# RTI-Dome.net
KiCad netlist of a schematic drawn in EAGLE
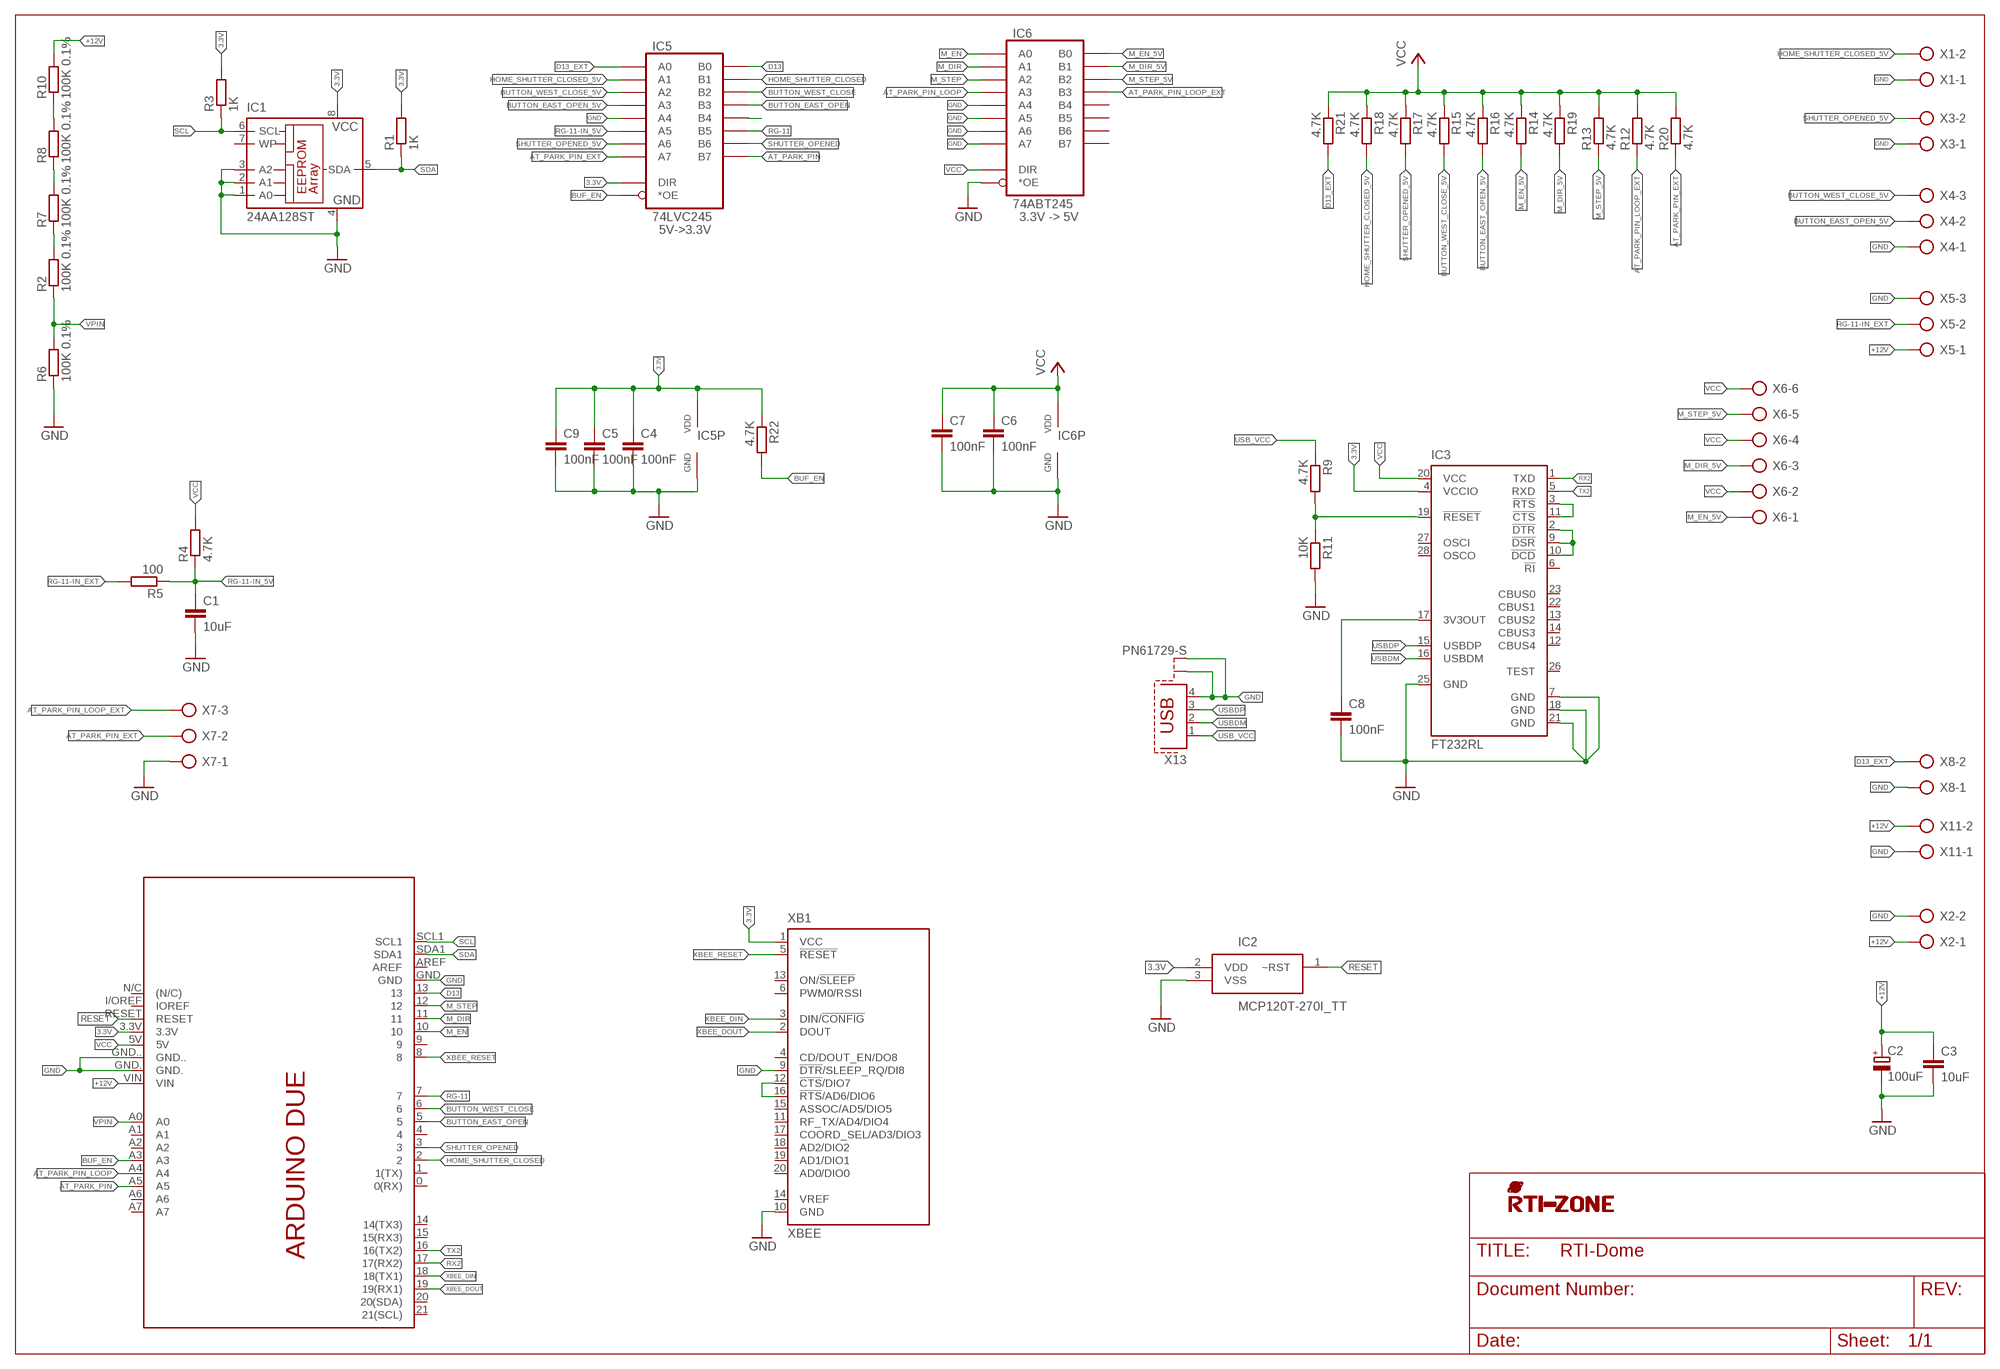
[diagram p0: schematic, sheet 1]

(export (version "E")
  (design (tool "Eeschema 10.0.6"))
  (components
    (comp (ref "C1")
      (value "10uF")
      (footprint "eagle-import:C0805")
      (libsource (lib "eagle-import") (part "C-EU'0805'"))
    )
    (comp (ref "C2")
      (value "100uF")
      (footprint "eagle-import:UD-10X10_NICHICON")
      (libsource (lib "eagle-import") (part "CPOL-EU"))
    )
    (comp (ref "C3")
      (value "10uF")
      (footprint "eagle-import:C0805")
      (libsource (lib "eagle-import") (part "C-EU'0805'"))
    )
    (comp (ref "C4")
      (value "100nF")
      (footprint "eagle-import:C0805")
      (libsource (lib "eagle-import") (part "C-EU'0805'"))
    )
    (comp (ref "C5")
      (value "100nF")
      (footprint "eagle-import:C0805")
      (libsource (lib "eagle-import") (part "C-EU'0805'"))
    )
    (comp (ref "C6")
      (value "100nF")
      (footprint "eagle-import:C0805")
      (libsource (lib "eagle-import") (part "C-EU'0805'"))
    )
    (comp (ref "C7")
      (value "100nF")
      (footprint "eagle-import:C0805")
      (libsource (lib "eagle-import") (part "C-EU'0805'"))
    )
    (comp (ref "C8")
      (value "100nF")
      (footprint "eagle-import:C0805")
      (libsource (lib "eagle-import") (part "C-EU'0805'"))
    )
    (comp (ref "C9")
      (value "100nF")
      (footprint "eagle-import:C0805")
      (libsource (lib "eagle-import") (part "C-EU'0805'"))
    )
    (comp (ref "IC1")
      (value "24AA128ST")
      (footprint "eagle-import:TSSOP8")
      (fields (field (name "MF") "MICROCHIP") (field (name "MPN") "24AA128-I/ST"))
      (libsource (lib "eagle-import") (part "24STAA128"))
    )
    (comp (ref "IC2")
      (value "MCP120T-270I_TT")
      (footprint "eagle-import:SOT95P237X112-3N")
      (fields
        (field (name "MANUFACTURER_PART_NUMBER") "MCP120T-270I/TT")
        (field (name "MOUSER_PART_NUMBER") "579-MCP120T-270I/TT")
      )
      (libsource (lib "eagle-import") (part "MCP120T-270I_TT"))
    )
    (comp (ref "IC3")
      (value "FT232RL")
      (footprint "eagle-import:SSOP28")
      (libsource (lib "eagle-import") (part "FT232RL"))
    )
    (comp (ref "IC5")
      (value "74LVC245")
      (footprint "eagle-import:TSSOP20")
      (libsource (lib "eagle-import") (part "74245LVC"))
    )
    (comp (ref "IC6")
      (value "74ABT245")
      (footprint "eagle-import:TSSOP20")
      (libsource (lib "eagle-import") (part "74245ABT"))
    )
    (comp (ref "PCB1")
      (value "ARDUINO_DUE_SHIELD_SHORT")
      (footprint "eagle-import:ARDUINO_DUE_SHIELD_SHORT")
      (libsource (lib "eagle-import") (part "ARDUINO_DUE_SHIELD_SHORT"))
    )
    (comp (ref "R1")
      (value "1K")
      (footprint "eagle-import:R0805")
      (libsource (lib "eagle-import") (part "R-EU'0805'"))
    )
    (comp (ref "R2")
      (value "100K 0.1%")
      (footprint "eagle-import:R0805")
      (libsource (lib "eagle-import") (part "R-EU'0805'"))
    )
    (comp (ref "R3")
      (value "1K")
      (footprint "eagle-import:R0805")
      (libsource (lib "eagle-import") (part "R-EU'0805'"))
    )
    (comp (ref "R4")
      (value "4.7K")
      (footprint "eagle-import:R0805")
      (libsource (lib "eagle-import") (part "R-EU'0805'"))
    )
    (comp (ref "R5")
      (value "100")
      (footprint "eagle-import:R0805")
      (libsource (lib "eagle-import") (part "R-EU'0805'"))
    )
    (comp (ref "R6")
      (value "100K 0.1%")
      (footprint "eagle-import:R0805")
      (libsource (lib "eagle-import") (part "R-EU'0805'"))
    )
    (comp (ref "R7")
      (value "100K 0.1%")
      (footprint "eagle-import:R0805")
      (libsource (lib "eagle-import") (part "R-EU'0805'"))
    )
    (comp (ref "R8")
      (value "100K 0.1%")
      (footprint "eagle-import:R0805")
      (libsource (lib "eagle-import") (part "R-EU'0805'"))
    )
    (comp (ref "R9")
      (value "4.7K")
      (footprint "eagle-import:R0805")
      (libsource (lib "eagle-import") (part "R-EU'0805'"))
    )
    (comp (ref "R10")
      (value "100K 0.1%")
      (footprint "eagle-import:R0805")
      (libsource (lib "eagle-import") (part "R-EU'0805'"))
    )
    (comp (ref "R11")
      (value "10K")
      (footprint "eagle-import:R0805")
      (libsource (lib "eagle-import") (part "R-EU'0805'"))
    )
    (comp (ref "R12")
      (value "4.7K")
      (footprint "eagle-import:R0805")
      (libsource (lib "eagle-import") (part "R-EU'0805'"))
    )
    (comp (ref "R13")
      (value "4.7K")
      (footprint "eagle-import:R0805")
      (libsource (lib "eagle-import") (part "R-EU'0805'"))
    )
    (comp (ref "R14")
      (value "4.7K")
      (footprint "eagle-import:R0805")
      (libsource (lib "eagle-import") (part "R-EU'0805'"))
    )
    (comp (ref "R15")
      (value "4.7K")
      (footprint "eagle-import:R0805")
      (libsource (lib "eagle-import") (part "R-EU'0805'"))
    )
    (comp (ref "R16")
      (value "4.7K")
      (footprint "eagle-import:R0805")
      (libsource (lib "eagle-import") (part "R-EU'0805'"))
    )
    (comp (ref "R17")
      (value "4.7K")
      (footprint "eagle-import:R0805")
      (libsource (lib "eagle-import") (part "R-EU'0805'"))
    )
    (comp (ref "R18")
      (value "4.7K")
      (footprint "eagle-import:R0805")
      (libsource (lib "eagle-import") (part "R-EU'0805'"))
    )
    (comp (ref "R19")
      (value "4.7K")
      (footprint "eagle-import:R0805")
      (libsource (lib "eagle-import") (part "R-EU'0805'"))
    )
    (comp (ref "R20")
      (value "4.7K")
      (footprint "eagle-import:R0805")
      (libsource (lib "eagle-import") (part "R-EU'0805'"))
    )
    (comp (ref "R21")
      (value "4.7K")
      (footprint "eagle-import:R0805")
      (libsource (lib "eagle-import") (part "R-EU'0805'"))
    )
    (comp (ref "R22")
      (value "4.7K")
      (footprint "eagle-import:R0805")
      (libsource (lib "eagle-import") (part "R-EU'0805'"))
    )
    (comp (ref "U$4")
      (value "RTI-LOGO_BIG")
      (footprint "eagle-import:LOGO_BIG")
      (libsource (lib "eagle-import") (part "RTI-LOGO_BIG"))
    )
    (comp (ref "X1")
      (value "AK500/2")
      (footprint "eagle-import:AK500_2")
      (libsource (lib "eagle-import") (part "AK500/2"))
    )
    (comp (ref "X2")
      (value "AK500/2")
      (footprint "eagle-import:AK500_2")
      (libsource (lib "eagle-import") (part "AK500/2"))
    )
    (comp (ref "X3")
      (value "AK500/2")
      (footprint "eagle-import:AK500_2")
      (libsource (lib "eagle-import") (part "AK500/2"))
    )
    (comp (ref "X4")
      (value "AK500/3")
      (footprint "eagle-import:AK500_3")
      (libsource (lib "eagle-import") (part "AK500/3"))
    )
    (comp (ref "X5")
      (value "AK500/3")
      (footprint "eagle-import:AK500_3")
      (libsource (lib "eagle-import") (part "AK500/3"))
    )
    (comp (ref "X6")
      (value "AK500/6")
      (footprint "eagle-import:AK500_6")
      (libsource (lib "eagle-import") (part "AK500/6"))
    )
    (comp (ref "X7")
      (value "AK500/3")
      (footprint "eagle-import:AK500_3")
      (libsource (lib "eagle-import") (part "AK500/3"))
    )
    (comp (ref "X8")
      (value "AK500/2")
      (footprint "eagle-import:AK500_2")
      (libsource (lib "eagle-import") (part "AK500/2"))
    )
    (comp (ref "X11")
      (value "AK500/2")
      (footprint "eagle-import:AK500_2")
      (libsource (lib "eagle-import") (part "AK500/2"))
    )
    (comp (ref "X13")
      (value "PN61729-S")
      (footprint "eagle-import:PN61729-S")
      (libsource (lib "eagle-import") (part "PN61729-S"))
    )
    (comp (ref "XB1")
      (value "XBEE")
      (footprint "eagle-import:XBEE")
      (fields (field (name "MPN") "XBP24-Z7UIT-004"))
      (libsource (lib "eagle-import") (part "XBEE"))
    )
  )
  (nets
    (net (code "1") (name "+12V") (class "Default")
      (node (ref "C2") (pin "+") (pinfunction "+_+") (pintype "passive"))
      (node (ref "C3") (pin "1") (pinfunction "1_1") (pintype "passive"))
      (node (ref "PCB1") (pin "VIN") (pinfunction "VIN_VIN") (pintype "bidirectional"))
      (node (ref "R10") (pin "2") (pinfunction "2_2") (pintype "passive"))
      (node (ref "X11") (pin "2") (pinfunction "KL_2") (pintype "passive"))
      (node (ref "X2") (pin "1") (pinfunction "KL_1") (pintype "passive"))
      (node (ref "X5") (pin "1") (pinfunction "KL_1") (pintype "passive"))
    )
    (net (code "2") (name "3.3V") (class "Default")
      (node (ref "C4") (pin "1") (pinfunction "1_1") (pintype "passive"))
      (node (ref "C5") (pin "1") (pinfunction "1_1") (pintype "passive"))
      (node (ref "C9") (pin "1") (pinfunction "1_1") (pintype "passive"))
      (node (ref "IC1") (pin "8") (pinfunction "VCC_8") (pintype "power_in"))
      (node (ref "IC2") (pin "2") (pinfunction "VDD_2") (pintype "bidirectional"))
      (node (ref "IC3") (pin "4") (pinfunction "VCCIO_4") (pintype "power_in"))
      (node (ref "IC5") (pin "P$1") (pinfunction "DIR_P$1") (pintype "input"))
      (node (ref "IC5") (pin "P$20") (pinfunction "VDD_P$20") (pintype "power_in"))
      (node (ref "PCB1") (pin "3.3V") (pinfunction "3.3V_3.3V") (pintype "bidirectional"))
      (node (ref "R1") (pin "2") (pinfunction "2_2") (pintype "passive"))
      (node (ref "R22") (pin "1") (pinfunction "1_1") (pintype "passive"))
      (node (ref "R3") (pin "2") (pinfunction "2_2") (pintype "passive"))
      (node (ref "XB1") (pin "1") (pinfunction "VCC_1") (pintype "power_in"))
    )
    (net (code "3") (name "AT_PARK_PIN") (class "Default")
      (node (ref "IC5") (pin "P$11") (pinfunction "B7_P$11") (pintype "bidirectional"))
      (node (ref "PCB1") (pin "A5") (pinfunction "A5_A5") (pintype "bidirectional"))
    )
    (net (code "4") (name "AT_PARK_PIN_EXT") (class "Default")
      (node (ref "IC5") (pin "P$9") (pinfunction "A7_P$9") (pintype "bidirectional"))
      (node (ref "R20") (pin "1") (pinfunction "1_1") (pintype "passive"))
      (node (ref "X7") (pin "2") (pinfunction "KL_2") (pintype "passive"))
    )
    (net (code "5") (name "AT_PARK_PIN_LOOP") (class "Default")
      (node (ref "IC6") (pin "P$5") (pinfunction "A3_P$5") (pintype "bidirectional"))
      (node (ref "PCB1") (pin "A4") (pinfunction "A4_A4") (pintype "bidirectional"))
    )
    (net (code "6") (name "AT_PARK_PIN_LOOP_EXT") (class "Default")
      (node (ref "IC6") (pin "P$15") (pinfunction "B3_P$15") (pintype "bidirectional"))
      (node (ref "R12") (pin "1") (pinfunction "1_1") (pintype "passive"))
      (node (ref "X7") (pin "3") (pinfunction "KL_3") (pintype "passive"))
    )
    (net (code "7") (name "BUF_EN") (class "Default")
      (node (ref "IC5") (pin "P$19") (pinfunction "*OE_P$19") (pintype "input"))
      (node (ref "PCB1") (pin "A3") (pinfunction "A3_A3") (pintype "bidirectional"))
      (node (ref "R22") (pin "2") (pinfunction "2_2") (pintype "passive"))
    )
    (net (code "8") (name "BUTTON_EAST_OPEN") (class "Default")
      (node (ref "IC5") (pin "P$15") (pinfunction "B3_P$15") (pintype "bidirectional"))
      (node (ref "PCB1") (pin "5") (pinfunction "5_5") (pintype "bidirectional"))
    )
    (net (code "9") (name "BUTTON_EAST_OPEN_5V") (class "Default")
      (node (ref "IC5") (pin "P$5") (pinfunction "A3_P$5") (pintype "bidirectional"))
      (node (ref "R16") (pin "2") (pinfunction "2_2") (pintype "passive"))
      (node (ref "X4") (pin "2") (pinfunction "KL_2") (pintype "passive"))
    )
    (net (code "10") (name "BUTTON_WEST_CLOSE") (class "Default")
      (node (ref "IC5") (pin "P$16") (pinfunction "B2_P$16") (pintype "bidirectional"))
      (node (ref "PCB1") (pin "6") (pinfunction "6_6") (pintype "bidirectional"))
    )
    (net (code "11") (name "BUTTON_WEST_CLOSE_5V") (class "Default")
      (node (ref "IC5") (pin "P$4") (pinfunction "A2_P$4") (pintype "bidirectional"))
      (node (ref "R15") (pin "2") (pinfunction "2_2") (pintype "passive"))
      (node (ref "X4") (pin "3") (pinfunction "KL_3") (pintype "passive"))
    )
    (net (code "12") (name "D13") (class "Default")
      (node (ref "IC5") (pin "P$18") (pinfunction "B0_P$18") (pintype "bidirectional"))
      (node (ref "PCB1") (pin "13") (pinfunction "13_13") (pintype "bidirectional"))
    )
    (net (code "13") (name "D13_EXT") (class "Default")
      (node (ref "IC5") (pin "P$2") (pinfunction "A0_P$2") (pintype "bidirectional"))
      (node (ref "R21") (pin "2") (pinfunction "2_2") (pintype "passive"))
      (node (ref "X8") (pin "2") (pinfunction "KL_2") (pintype "passive"))
    )
    (net (code "14") (name "GND") (class "Default")
      (node (ref "C1") (pin "2") (pinfunction "2_2") (pintype "passive"))
      (node (ref "C2") (pin "-") (pinfunction "-_-") (pintype "passive"))
      (node (ref "C3") (pin "2") (pinfunction "2_2") (pintype "passive"))
      (node (ref "C4") (pin "2") (pinfunction "2_2") (pintype "passive"))
      (node (ref "C5") (pin "2") (pinfunction "2_2") (pintype "passive"))
      (node (ref "C6") (pin "2") (pinfunction "2_2") (pintype "passive"))
      (node (ref "C7") (pin "2") (pinfunction "2_2") (pintype "passive"))
      (node (ref "C8") (pin "2") (pinfunction "2_2") (pintype "passive"))
      (node (ref "C9") (pin "2") (pinfunction "2_2") (pintype "passive"))
      (node (ref "IC1") (pin "1") (pinfunction "A0_1") (pintype "input"))
      (node (ref "IC1") (pin "2") (pinfunction "A1_2") (pintype "input"))
      (node (ref "IC1") (pin "3") (pinfunction "A2_3") (pintype "input"))
      (node (ref "IC1") (pin "4") (pinfunction "GND_4") (pintype "power_in"))
      (node (ref "IC2") (pin "3") (pinfunction "VSS_3") (pintype "bidirectional"))
      (node (ref "IC3") (pin "18") (pinfunction "GND_18") (pintype "power_in"))
      (node (ref "IC3") (pin "21") (pinfunction "GND_21") (pintype "power_in"))
      (node (ref "IC3") (pin "25") (pinfunction "GND_25") (pintype "power_in"))
      (node (ref "IC3") (pin "7") (pinfunction "GND_7") (pintype "power_in"))
      (node (ref "IC5") (pin "P$10") (pinfunction "GND_P$10") (pintype "power_in"))
      (node (ref "IC5") (pin "P$6") (pinfunction "A4_P$6") (pintype "bidirectional"))
      (node (ref "IC6") (pin "P$10") (pinfunction "GND_P$10") (pintype "power_in"))
      (node (ref "IC6") (pin "P$19") (pinfunction "*OE_P$19") (pintype "input"))
      (node (ref "IC6") (pin "P$6") (pinfunction "A4_P$6") (pintype "bidirectional"))
      (node (ref "IC6") (pin "P$7") (pinfunction "A5_P$7") (pintype "bidirectional"))
      (node (ref "IC6") (pin "P$8") (pinfunction "A6_P$8") (pintype "bidirectional"))
      (node (ref "IC6") (pin "P$9") (pinfunction "A7_P$9") (pintype "bidirectional"))
      (node (ref "PCB1") (pin "GND") (pinfunction "GND_GND") (pintype "bidirectional"))
      (node (ref "PCB1") (pin "GND.") (pinfunction "GND._GND.") (pintype "bidirectional"))
      (node (ref "PCB1") (pin "GND..") (pinfunction "GND.._GND..") (pintype "bidirectional"))
      (node (ref "R11") (pin "2") (pinfunction "2_2") (pintype "passive"))
      (node (ref "R6") (pin "1") (pinfunction "1_1") (pintype "passive"))
      (node (ref "X1") (pin "1") (pinfunction "KL_1") (pintype "passive"))
      (node (ref "X11") (pin "1") (pinfunction "KL_1") (pintype "passive"))
      (node (ref "X13") (pin "4") (pinfunction "4_4") (pintype "passive"))
      (node (ref "X13") (pin "S1") (pinfunction "S1_S1") (pintype "passive"))
      (node (ref "X13") (pin "S2") (pinfunction "S2_S2") (pintype "passive"))
      (node (ref "X2") (pin "2") (pinfunction "KL_2") (pintype "passive"))
      (node (ref "X3") (pin "1") (pinfunction "KL_1") (pintype "passive"))
      (node (ref "X4") (pin "1") (pinfunction "KL_1") (pintype "passive"))
      (node (ref "X5") (pin "3") (pinfunction "KL_3") (pintype "passive"))
      (node (ref "X7") (pin "1") (pinfunction "KL_1") (pintype "passive"))
      (node (ref "X8") (pin "1") (pinfunction "KL_1") (pintype "passive"))
      (node (ref "XB1") (pin "10") (pinfunction "GND_10") (pintype "power_in"))
      (node (ref "XB1") (pin "9") (pinfunction "~{DTR}/SLEEP_RQ/DI8_9") (pintype "bidirectional"))
    )
    (net (code "15") (name "HOME_SHUTTER_CLOSED") (class "Default")
      (node (ref "IC5") (pin "P$17") (pinfunction "B1_P$17") (pintype "bidirectional"))
      (node (ref "PCB1") (pin "2") (pinfunction "2_2") (pintype "bidirectional"))
    )
    (net (code "16") (name "HOME_SHUTTER_CLOSED_5V") (class "Default")
      (node (ref "IC5") (pin "P$3") (pinfunction "A1_P$3") (pintype "bidirectional"))
      (node (ref "R18") (pin "2") (pinfunction "2_2") (pintype "passive"))
      (node (ref "X1") (pin "2") (pinfunction "KL_2") (pintype "passive"))
    )
    (net (code "17") (name "M_DIR") (class "Default")
      (node (ref "IC6") (pin "P$3") (pinfunction "A1_P$3") (pintype "bidirectional"))
      (node (ref "PCB1") (pin "11") (pinfunction "11_11") (pintype "bidirectional"))
    )
    (net (code "18") (name "M_DIR_5V") (class "Default")
      (node (ref "IC6") (pin "P$17") (pinfunction "B1_P$17") (pintype "bidirectional"))
      (node (ref "R19") (pin "2") (pinfunction "2_2") (pintype "passive"))
      (node (ref "X6") (pin "3") (pinfunction "KL_3") (pintype "passive"))
    )
    (net (code "19") (name "M_EN") (class "Default")
      (node (ref "IC6") (pin "P$2") (pinfunction "A0_P$2") (pintype "bidirectional"))
      (node (ref "PCB1") (pin "10") (pinfunction "10_10") (pintype "bidirectional"))
    )
    (net (code "20") (name "M_EN_5V") (class "Default")
      (node (ref "IC6") (pin "P$18") (pinfunction "B0_P$18") (pintype "bidirectional"))
      (node (ref "R14") (pin "2") (pinfunction "2_2") (pintype "passive"))
      (node (ref "X6") (pin "1") (pinfunction "KL_1") (pintype "passive"))
    )
    (net (code "21") (name "M_STEP") (class "Default")
      (node (ref "IC6") (pin "P$4") (pinfunction "A2_P$4") (pintype "bidirectional"))
      (node (ref "PCB1") (pin "12") (pinfunction "12_12") (pintype "bidirectional"))
    )
    (net (code "22") (name "M_STEP_5V") (class "Default")
      (node (ref "IC6") (pin "P$16") (pinfunction "B2_P$16") (pintype "bidirectional"))
      (node (ref "R13") (pin "1") (pinfunction "1_1") (pintype "passive"))
      (node (ref "X6") (pin "5") (pinfunction "KL_5") (pintype "passive"))
    )
    (net (code "23") (name "Net-(IC3-3V3OUT)") (class "Default")
      (node (ref "C8") (pin "1") (pinfunction "1_1") (pintype "passive"))
      (node (ref "IC3") (pin "17") (pinfunction "3V3OUT_17") (pintype "output"))
    )
    (net (code "24") (name "Net-(IC3-~{CTS})") (class "Default")
      (node (ref "IC3") (pin "11") (pinfunction "~{CTS}_11") (pintype "input"))
      (node (ref "IC3") (pin "3") (pinfunction "~{RTS}_3") (pintype "output"))
    )
    (net (code "25") (name "Net-(IC3-~{DCD})") (class "Default")
      (node (ref "IC3") (pin "10") (pinfunction "~{DCD}_10") (pintype "input"))
      (node (ref "IC3") (pin "2") (pinfunction "~{DTR}_2") (pintype "output"))
      (node (ref "IC3") (pin "9") (pinfunction "~{DSR}_9") (pintype "input"))
    )
    (net (code "26") (name "Net-(IC3-~{RESET})") (class "Default")
      (node (ref "IC3") (pin "19") (pinfunction "~{RESET}_19") (pintype "input"))
      (node (ref "R11") (pin "1") (pinfunction "1_1") (pintype "passive"))
      (node (ref "R9") (pin "2") (pinfunction "2_2") (pintype "passive"))
    )
    (net (code "27") (name "Net-(R2-Pad2)") (class "Default")
      (node (ref "R2") (pin "2") (pinfunction "2_2") (pintype "passive"))
      (node (ref "R7") (pin "1") (pinfunction "1_1") (pintype "passive"))
    )
    (net (code "28") (name "Net-(R7-Pad2)") (class "Default")
      (node (ref "R7") (pin "2") (pinfunction "2_2") (pintype "passive"))
      (node (ref "R8") (pin "1") (pinfunction "1_1") (pintype "passive"))
    )
    (net (code "29") (name "Net-(R10-Pad1)") (class "Default")
      (node (ref "R10") (pin "1") (pinfunction "1_1") (pintype "passive"))
      (node (ref "R8") (pin "2") (pinfunction "2_2") (pintype "passive"))
    )
    (net (code "30") (name "Net-(XB1-~{CTS}{slash}DIO7)") (class "Default")
      (node (ref "XB1") (pin "12") (pinfunction "~{CTS}/DIO7_12") (pintype "bidirectional"))
      (node (ref "XB1") (pin "16") (pinfunction "~{RTS}/AD6/DIO6_16") (pintype "bidirectional"))
    )
    (net (code "31") (name "RESET") (class "Default")
      (node (ref "IC2") (pin "1") (pinfunction "~{RST}_1") (pintype "bidirectional"))
      (node (ref "PCB1") (pin "RESET") (pinfunction "RESET_RESET") (pintype "bidirectional"))
    )
    (net (code "32") (name "RG-11") (class "Default")
      (node (ref "IC5") (pin "P$13") (pinfunction "B5_P$13") (pintype "bidirectional"))
      (node (ref "PCB1") (pin "7") (pinfunction "7_7") (pintype "bidirectional"))
    )
    (net (code "33") (name "RG-11-IN_5V") (class "Default")
      (node (ref "C1") (pin "1") (pinfunction "1_1") (pintype "passive"))
      (node (ref "IC5") (pin "P$7") (pinfunction "A5_P$7") (pintype "bidirectional"))
      (node (ref "R4") (pin "1") (pinfunction "1_1") (pintype "passive"))
      (node (ref "R5") (pin "1") (pinfunction "1_1") (pintype "passive"))
    )
    (net (code "34") (name "RG-11-IN_EXT") (class "Default")
      (node (ref "R5") (pin "2") (pinfunction "2_2") (pintype "passive"))
      (node (ref "X5") (pin "2") (pinfunction "KL_2") (pintype "passive"))
    )
    (net (code "35") (name "RX2") (class "Default")
      (node (ref "IC3") (pin "1") (pinfunction "TXD_1") (pintype "output"))
      (node (ref "PCB1") (pin "17") (pinfunction "17(RX2)_17") (pintype "bidirectional"))
    )
    (net (code "36") (name "SCL") (class "Default")
      (node (ref "IC1") (pin "6") (pinfunction "SCL_6") (pintype "input"))
      (node (ref "PCB1") (pin "SCL1") (pinfunction "SCL1_SCL1") (pintype "bidirectional"))
      (node (ref "R3") (pin "1") (pinfunction "1_1") (pintype "passive"))
    )
    (net (code "37") (name "SDA") (class "Default")
      (node (ref "IC1") (pin "5") (pinfunction "SDA_5") (pintype "bidirectional"))
      (node (ref "PCB1") (pin "SDA1") (pinfunction "SDA1_SDA1") (pintype "bidirectional"))
      (node (ref "R1") (pin "1") (pinfunction "1_1") (pintype "passive"))
    )
    (net (code "38") (name "SHUTTER_OPENED") (class "Default")
      (node (ref "IC5") (pin "P$12") (pinfunction "B6_P$12") (pintype "bidirectional"))
      (node (ref "PCB1") (pin "3") (pinfunction "3_3") (pintype "bidirectional"))
    )
    (net (code "39") (name "SHUTTER_OPENED_5V") (class "Default")
      (node (ref "IC5") (pin "P$8") (pinfunction "A6_P$8") (pintype "bidirectional"))
      (node (ref "R17") (pin "2") (pinfunction "2_2") (pintype "passive"))
      (node (ref "X3") (pin "2") (pinfunction "KL_2") (pintype "passive"))
    )
    (net (code "40") (name "TX2") (class "Default")
      (node (ref "IC3") (pin "5") (pinfunction "RXD_5") (pintype "input"))
      (node (ref "PCB1") (pin "16") (pinfunction "16(TX2)_16") (pintype "bidirectional"))
    )
    (net (code "41") (name "USBDM") (class "Default")
      (node (ref "IC3") (pin "16") (pinfunction "USBDM_16") (pintype "bidirectional"))
      (node (ref "X13") (pin "2") (pinfunction "2_2") (pintype "passive"))
    )
    (net (code "42") (name "USBDP") (class "Default")
      (node (ref "IC3") (pin "15") (pinfunction "USBDP_15") (pintype "bidirectional"))
      (node (ref "X13") (pin "3") (pinfunction "3_3") (pintype "passive"))
    )
    (net (code "43") (name "USB_VCC") (class "Default")
      (node (ref "R9") (pin "1") (pinfunction "1_1") (pintype "passive"))
      (node (ref "X13") (pin "1") (pinfunction "1_1") (pintype "passive"))
    )
    (net (code "44") (name "VCC") (class "Default")
      (node (ref "C6") (pin "1") (pinfunction "1_1") (pintype "passive"))
      (node (ref "C7") (pin "1") (pinfunction "1_1") (pintype "passive"))
      (node (ref "IC3") (pin "20") (pinfunction "VCC_20") (pintype "power_in"))
      (node (ref "IC6") (pin "P$1") (pinfunction "DIR_P$1") (pintype "input"))
      (node (ref "IC6") (pin "P$20") (pinfunction "VDD_P$20") (pintype "power_in"))
      (node (ref "PCB1") (pin "5V") (pinfunction "5V_5V") (pintype "bidirectional"))
      (node (ref "R12") (pin "2") (pinfunction "2_2") (pintype "passive"))
      (node (ref "R13") (pin "2") (pinfunction "2_2") (pintype "passive"))
      (node (ref "R14") (pin "1") (pinfunction "1_1") (pintype "passive"))
      (node (ref "R15") (pin "1") (pinfunction "1_1") (pintype "passive"))
      (node (ref "R16") (pin "1") (pinfunction "1_1") (pintype "passive"))
      (node (ref "R17") (pin "1") (pinfunction "1_1") (pintype "passive"))
      (node (ref "R18") (pin "1") (pinfunction "1_1") (pintype "passive"))
      (node (ref "R19") (pin "1") (pinfunction "1_1") (pintype "passive"))
      (node (ref "R20") (pin "2") (pinfunction "2_2") (pintype "passive"))
      (node (ref "R21") (pin "1") (pinfunction "1_1") (pintype "passive"))
      (node (ref "R4") (pin "2") (pinfunction "2_2") (pintype "passive"))
      (node (ref "X6") (pin "2") (pinfunction "KL_2") (pintype "passive"))
      (node (ref "X6") (pin "4") (pinfunction "KL_4") (pintype "passive"))
      (node (ref "X6") (pin "6") (pinfunction "KL_6") (pintype "passive"))
    )
    (net (code "45") (name "VPIN") (class "Default")
      (node (ref "PCB1") (pin "A0") (pinfunction "A0_A0") (pintype "bidirectional"))
      (node (ref "R2") (pin "1") (pinfunction "1_1") (pintype "passive"))
      (node (ref "R6") (pin "2") (pinfunction "2_2") (pintype "passive"))
    )
    (net (code "46") (name "XBEE_DIN") (class "Default")
      (node (ref "PCB1") (pin "18") (pinfunction "18(TX1)_18") (pintype "bidirectional"))
      (node (ref "XB1") (pin "3") (pinfunction "DIN/~{CONFIG}_3") (pintype "input"))
    )
    (net (code "47") (name "XBEE_DOUT") (class "Default")
      (node (ref "PCB1") (pin "19") (pinfunction "19(RX1)_19") (pintype "bidirectional"))
      (node (ref "XB1") (pin "2") (pinfunction "DOUT_2") (pintype "output"))
    )
    (net (code "48") (name "XBEE_RESET") (class "Default")
      (node (ref "PCB1") (pin "8") (pinfunction "8_8") (pintype "bidirectional"))
      (node (ref "XB1") (pin "5") (pinfunction "~{RESET}_5") (pintype "input"))
    )
    (net (code "49") (name "unconnected-(IC1-WP-Pad7)") (class "Default")
      (node (ref "IC1") (pin "7") (pinfunction "WP_7") (pintype "input"))
    )
    (net (code "50") (name "unconnected-(IC3-CBUS0-Pad23)") (class "Default")
      (node (ref "IC3") (pin "23") (pinfunction "CBUS0_23") (pintype "bidirectional"))
    )
    (net (code "51") (name "unconnected-(IC3-CBUS1-Pad22)") (class "Default")
      (node (ref "IC3") (pin "22") (pinfunction "CBUS1_22") (pintype "bidirectional"))
    )
    (net (code "52") (name "unconnected-(IC3-CBUS2-Pad13)") (class "Default")
      (node (ref "IC3") (pin "13") (pinfunction "CBUS2_13") (pintype "bidirectional"))
    )
    (net (code "53") (name "unconnected-(IC3-CBUS3-Pad14)") (class "Default")
      (node (ref "IC3") (pin "14") (pinfunction "CBUS3_14") (pintype "bidirectional"))
    )
    (net (code "54") (name "unconnected-(IC3-CBUS4-Pad12)") (class "Default")
      (node (ref "IC3") (pin "12") (pinfunction "CBUS4_12") (pintype "bidirectional"))
    )
    (net (code "55") (name "unconnected-(IC3-OSCI-Pad27)") (class "Default")
      (node (ref "IC3") (pin "27") (pinfunction "OSCI_27") (pintype "input"))
    )
    (net (code "56") (name "unconnected-(IC3-OSCO-Pad28)") (class "Default")
      (node (ref "IC3") (pin "28") (pinfunction "OSCO_28") (pintype "output"))
    )
    (net (code "57") (name "unconnected-(IC3-TEST-Pad26)") (class "Default")
      (node (ref "IC3") (pin "26") (pinfunction "TEST_26") (pintype "input"))
    )
    (net (code "58") (name "unconnected-(IC3-~{RI}-Pad6)") (class "Default")
      (node (ref "IC3") (pin "6") (pinfunction "~{RI}_6") (pintype "input"))
    )
    (net (code "59") (name "unconnected-(IC5A-B4-PadP$14)") (class "Default")
      (node (ref "IC5") (pin "P$14") (pinfunction "B4_P$14") (pintype "bidirectional"))
    )
    (net (code "60") (name "unconnected-(IC6A-B4-PadP$14)") (class "Default")
      (node (ref "IC6") (pin "P$14") (pinfunction "B4_P$14") (pintype "bidirectional"))
    )
    (net (code "61") (name "unconnected-(IC6A-B5-PadP$13)") (class "Default")
      (node (ref "IC6") (pin "P$13") (pinfunction "B5_P$13") (pintype "bidirectional"))
    )
    (net (code "62") (name "unconnected-(IC6A-B6-PadP$12)") (class "Default")
      (node (ref "IC6") (pin "P$12") (pinfunction "B6_P$12") (pintype "bidirectional"))
    )
    (net (code "63") (name "unconnected-(IC6A-B7-PadP$11)") (class "Default")
      (node (ref "IC6") (pin "P$11") (pinfunction "B7_P$11") (pintype "bidirectional"))
    )
    (net (code "64") (name "unconnected-(PCB1-(N{slash}C)-PadN{slash}C)") (class "Default")
      (node (ref "PCB1") (pin "N/C") (pinfunction "(N/C)_N/C") (pintype "bidirectional"))
    )
    (net (code "65") (name "unconnected-(PCB1-0(RX)-Pad0)") (class "Default")
      (node (ref "PCB1") (pin "0") (pinfunction "0(RX)_0") (pintype "bidirectional"))
    )
    (net (code "66") (name "unconnected-(PCB1-1(TX)-Pad1)") (class "Default")
      (node (ref "PCB1") (pin "1") (pinfunction "1(TX)_1") (pintype "bidirectional"))
    )
    (net (code "67") (name "unconnected-(PCB1-14(TX3)-Pad14)") (class "Default")
      (node (ref "PCB1") (pin "14") (pinfunction "14(TX3)_14") (pintype "bidirectional"))
    )
    (net (code "68") (name "unconnected-(PCB1-15(RX3)-Pad15)") (class "Default")
      (node (ref "PCB1") (pin "15") (pinfunction "15(RX3)_15") (pintype "bidirectional"))
    )
    (net (code "69") (name "unconnected-(PCB1-20(SDA)-Pad20)") (class "Default")
      (node (ref "PCB1") (pin "20") (pinfunction "20(SDA)_20") (pintype "bidirectional"))
    )
    (net (code "70") (name "unconnected-(PCB1-21(SCL)-Pad21)") (class "Default")
      (node (ref "PCB1") (pin "21") (pinfunction "21(SCL)_21") (pintype "bidirectional"))
    )
    (net (code "71") (name "unconnected-(PCB1-IOREF-PadI{slash}OREF)") (class "Default")
      (node (ref "PCB1") (pin "I/OREF") (pinfunction "IOREF_I/OREF") (pintype "bidirectional"))
    )
    (net (code "72") (name "unconnected-(PCB1-Pad4)") (class "Default")
      (node (ref "PCB1") (pin "4") (pinfunction "4_4") (pintype "bidirectional"))
    )
    (net (code "73") (name "unconnected-(PCB1-Pad9)") (class "Default")
      (node (ref "PCB1") (pin "9") (pinfunction "9_9") (pintype "bidirectional"))
    )
    (net (code "74") (name "unconnected-(PCB1-PadA1)") (class "Default")
      (node (ref "PCB1") (pin "A1") (pinfunction "A1_A1") (pintype "bidirectional"))
    )
    (net (code "75") (name "unconnected-(PCB1-PadA2)") (class "Default")
      (node (ref "PCB1") (pin "A2") (pinfunction "A2_A2") (pintype "bidirectional"))
    )
    (net (code "76") (name "unconnected-(PCB1-PadA6)") (class "Default")
      (node (ref "PCB1") (pin "A6") (pinfunction "A6_A6") (pintype "bidirectional"))
    )
    (net (code "77") (name "unconnected-(PCB1-PadA7)") (class "Default")
      (node (ref "PCB1") (pin "A7") (pinfunction "A7_A7") (pintype "bidirectional"))
    )
    (net (code "78") (name "unconnected-(PCB1-PadAREF)") (class "Default")
      (node (ref "PCB1") (pin "AREF") (pinfunction "AREF_AREF") (pintype "bidirectional"))
    )
    (net (code "79") (name "unconnected-(XB1-AD0{slash}DIO0-Pad20)") (class "Default")
      (node (ref "XB1") (pin "20") (pinfunction "AD0/DIO0_20") (pintype "bidirectional"))
    )
    (net (code "80") (name "unconnected-(XB1-AD1{slash}DIO1-Pad19)") (class "Default")
      (node (ref "XB1") (pin "19") (pinfunction "AD1/DIO1_19") (pintype "bidirectional"))
    )
    (net (code "81") (name "unconnected-(XB1-AD2{slash}DIO2-Pad18)") (class "Default")
      (node (ref "XB1") (pin "18") (pinfunction "AD2/DIO2_18") (pintype "bidirectional"))
    )
    (net (code "82") (name "unconnected-(XB1-ASSOC{slash}AD5{slash}DIO5-Pad15)") (class "Default")
      (node (ref "XB1") (pin "15") (pinfunction "ASSOC/AD5/DIO5_15") (pintype "bidirectional"))
    )
    (net (code "83") (name "unconnected-(XB1-CD{slash}DOUT_EN{slash}DO8-Pad4)") (class "Default")
      (node (ref "XB1") (pin "4") (pinfunction "CD/DOUT_EN/DO8_4") (pintype "output"))
    )
    (net (code "84") (name "unconnected-(XB1-COORD_SEL{slash}AD3{slash}DIO3-Pad17)") (class "Default")
      (node (ref "XB1") (pin "17") (pinfunction "COORD_SEL/AD3/DIO3_17") (pintype "bidirectional"))
    )
    (net (code "85") (name "unconnected-(XB1-ON{slash}~{SLEEP}-Pad13)") (class "Default")
      (node (ref "XB1") (pin "13") (pinfunction "ON/~{SLEEP}_13") (pintype "output"))
    )
    (net (code "86") (name "unconnected-(XB1-PWM0{slash}RSSI-Pad6)") (class "Default")
      (node (ref "XB1") (pin "6") (pinfunction "PWM0/RSSI_6") (pintype "output"))
    )
    (net (code "87") (name "unconnected-(XB1-RF_TX{slash}AD4{slash}DIO4-Pad11)") (class "Default")
      (node (ref "XB1") (pin "11") (pinfunction "RF_TX/AD4/DIO4_11") (pintype "bidirectional"))
    )
    (net (code "88") (name "unconnected-(XB1-VREF-Pad14)") (class "Default")
      (node (ref "XB1") (pin "14") (pinfunction "VREF_14") (pintype "input"))
    )
  )
)
